# v2_1.net
KiCad netlist of a schematic drawn in EAGLE
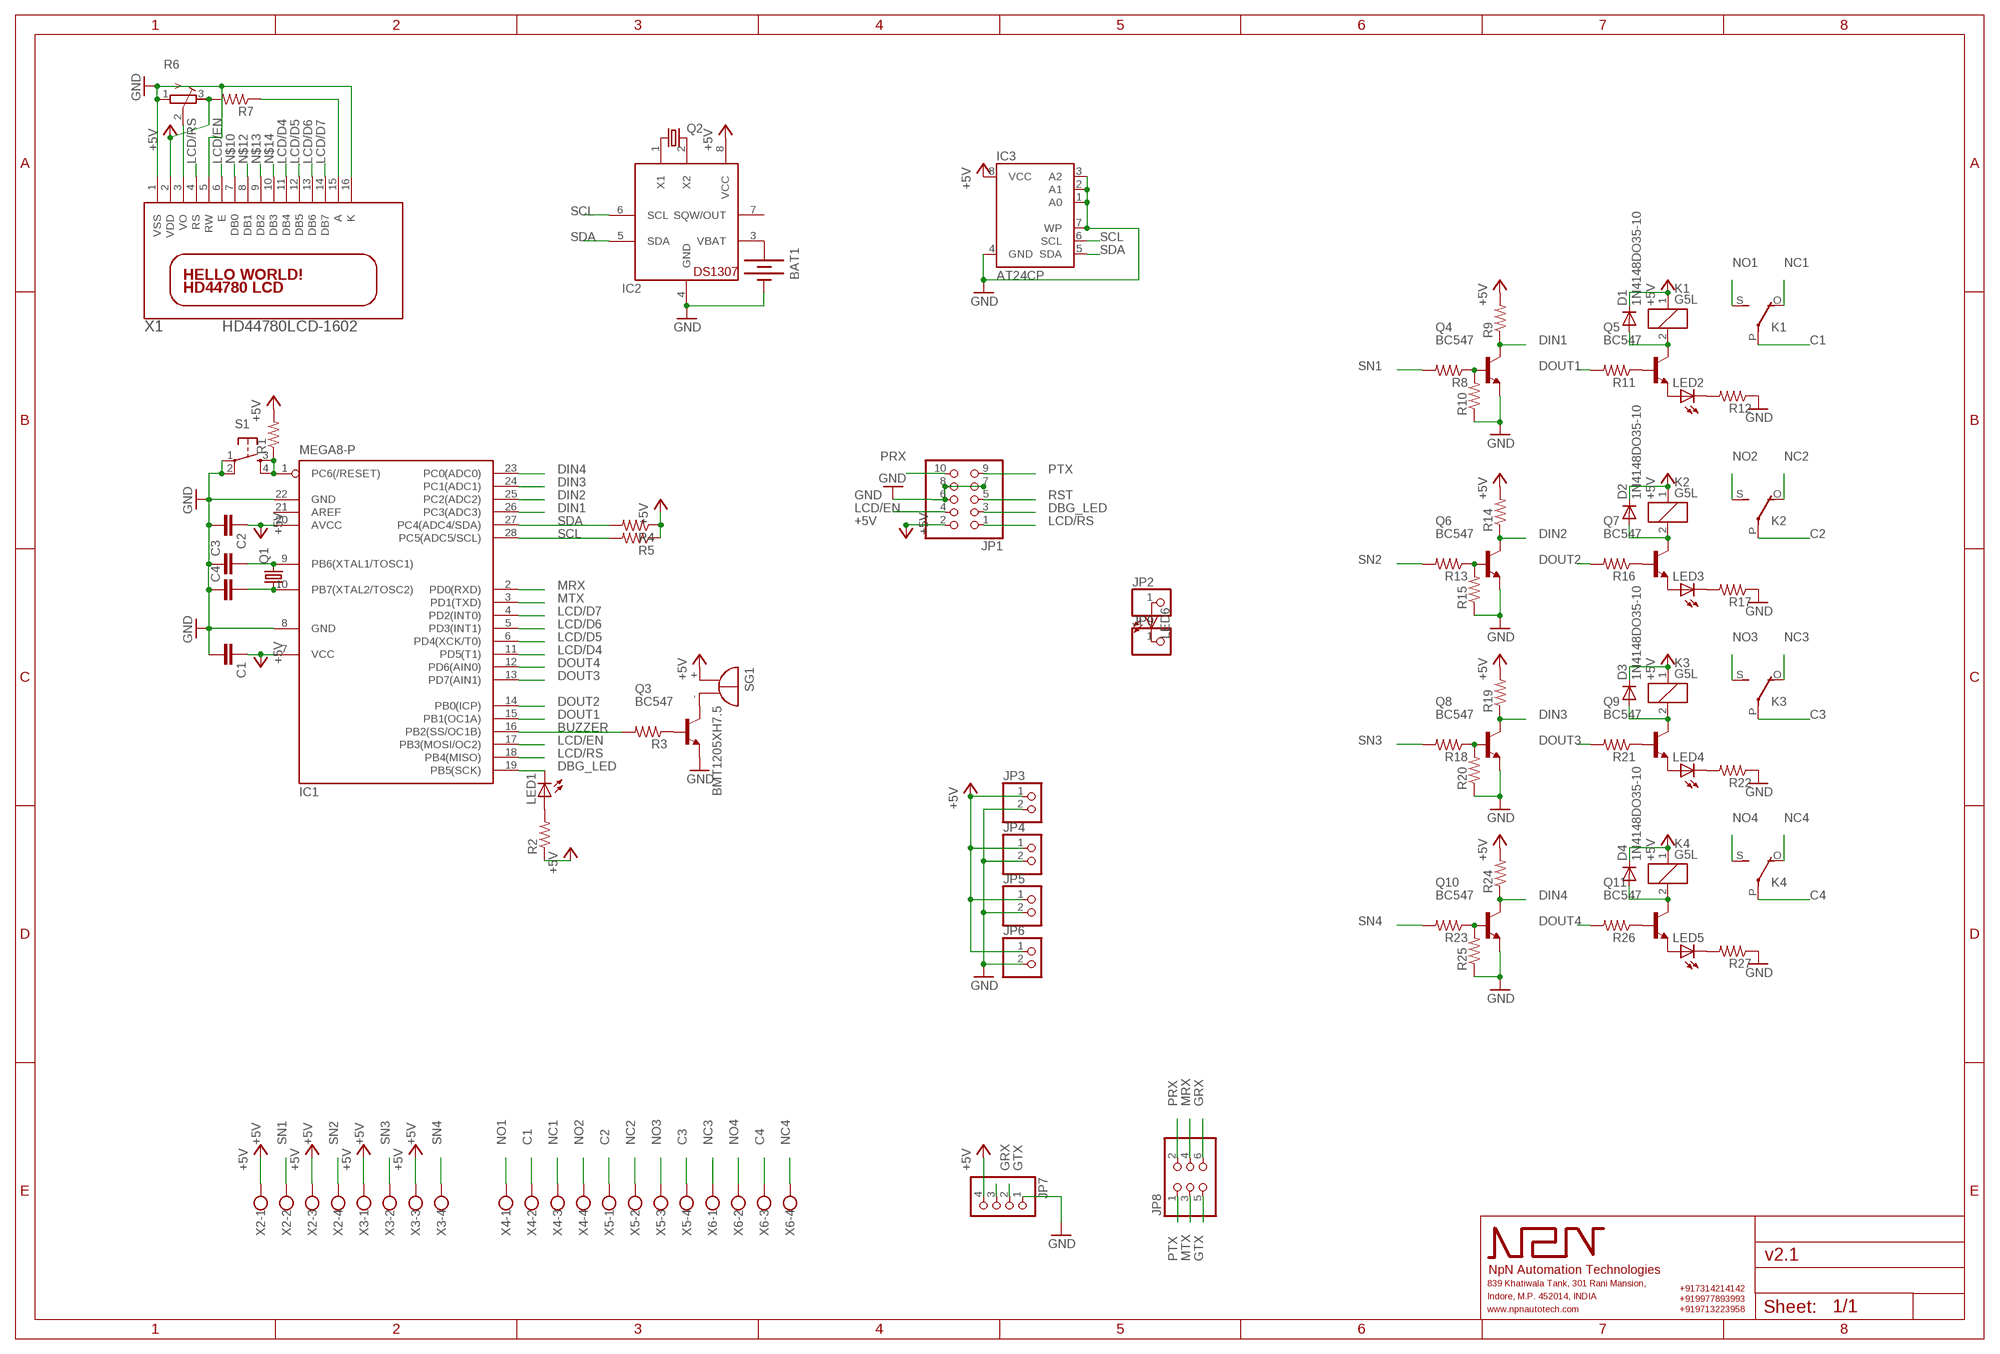
[diagram p0: schematic, sheet 1]

(export (version "E")
  (design (tool "Eeschema 10.0.6"))
  (components
    (comp (ref "BAT1")
      (value "BATTERY20PTH")
      (footprint "eagle-import:BATTCOM_20MM_PTH")
      (libsource (lib "eagle-import") (part "BATTERY20PTH"))
    )
    (comp (ref "C1")
      (value "C-EU050-025X075")
      (footprint "eagle-import:C050-025X075")
      (libsource (lib "eagle-import") (part "C-EU050-025X075"))
    )
    (comp (ref "C2")
      (value "C-EU050-025X075")
      (footprint "eagle-import:C050-025X075")
      (libsource (lib "eagle-import") (part "C-EU050-025X075"))
    )
    (comp (ref "C3")
      (value "C-EU050-025X075")
      (footprint "eagle-import:C050-025X075")
      (libsource (lib "eagle-import") (part "C-EU050-025X075"))
    )
    (comp (ref "C4")
      (value "C-EU050-025X075")
      (footprint "eagle-import:C050-025X075")
      (libsource (lib "eagle-import") (part "C-EU050-025X075"))
    )
    (comp (ref "D1")
      (value "1N4148DO35-10")
      (footprint "eagle-import:DO35-10")
      (libsource (lib "eagle-import") (part "1N4148DO35-10"))
    )
    (comp (ref "D2")
      (value "1N4148DO35-10")
      (footprint "eagle-import:DO35-10")
      (libsource (lib "eagle-import") (part "1N4148DO35-10"))
    )
    (comp (ref "D3")
      (value "1N4148DO35-10")
      (footprint "eagle-import:DO35-10")
      (libsource (lib "eagle-import") (part "1N4148DO35-10"))
    )
    (comp (ref "D4")
      (value "1N4148DO35-10")
      (footprint "eagle-import:DO35-10")
      (libsource (lib "eagle-import") (part "1N4148DO35-10"))
    )
    (comp (ref "IC1")
      (value "MEGA8-P")
      (footprint "eagle-import:DIL28-3")
      (libsource (lib "eagle-import") (part "MEGA8-P"))
    )
    (comp (ref "IC2")
      (value "DS1307")
      (footprint "eagle-import:DIL08")
      (libsource (lib "eagle-import") (part "DS1307"))
    )
    (comp (ref "IC3")
      (value "AT24CP")
      (footprint "eagle-import:DIL08")
      (fields (field (name "MPN") "AT24C1024BW-SH-B"))
      (libsource (lib "eagle-import") (part "AT24CP"))
    )
    (comp (ref "JP1")
      (value "PINHD-2X5")
      (footprint "eagle-import:2X05")
      (libsource (lib "eagle-import") (part "PINHD-2X5"))
    )
    (comp (ref "JP2")
      (value "PINHD-1X1")
      (footprint "eagle-import:1X01")
      (libsource (lib "eagle-import") (part "PINHD-1X1"))
    )
    (comp (ref "JP3")
      (value "PINHD-1X2")
      (footprint "eagle-import:1X02")
      (libsource (lib "eagle-import") (part "PINHD-1X2"))
    )
    (comp (ref "JP4")
      (value "PINHD-1X2")
      (footprint "eagle-import:1X02")
      (libsource (lib "eagle-import") (part "PINHD-1X2"))
    )
    (comp (ref "JP5")
      (value "PINHD-1X2")
      (footprint "eagle-import:1X02")
      (libsource (lib "eagle-import") (part "PINHD-1X2"))
    )
    (comp (ref "JP6")
      (value "PINHD-1X2")
      (footprint "eagle-import:1X02")
      (libsource (lib "eagle-import") (part "PINHD-1X2"))
    )
    (comp (ref "JP7")
      (value "PINHD-1X4")
      (footprint "eagle-import:1X04")
      (libsource (lib "eagle-import") (part "PINHD-1X4"))
    )
    (comp (ref "JP8")
      (value "PINHD-2X3")
      (footprint "eagle-import:2X03")
      (libsource (lib "eagle-import") (part "PINHD-2X3"))
    )
    (comp (ref "JP9")
      (value "PINHD-1X1")
      (footprint "eagle-import:1X01")
      (libsource (lib "eagle-import") (part "PINHD-1X1"))
    )
    (comp (ref "K1")
      (value "G5L")
      (footprint "eagle-import:G5LE")
      (libsource (lib "eagle-import") (part "G5L"))
    )
    (comp (ref "K2")
      (value "G5L")
      (footprint "eagle-import:G5LE")
      (libsource (lib "eagle-import") (part "G5L"))
    )
    (comp (ref "K3")
      (value "G5L")
      (footprint "eagle-import:G5LE")
      (libsource (lib "eagle-import") (part "G5L"))
    )
    (comp (ref "K4")
      (value "G5L")
      (footprint "eagle-import:G5LE")
      (libsource (lib "eagle-import") (part "G5L"))
    )
    (comp (ref "LED1")
      (value "LED5MM")
      (footprint "eagle-import:LED5MM")
      (libsource (lib "eagle-import") (part "LED5MM"))
    )
    (comp (ref "LED2")
      (value "LED5MM")
      (footprint "eagle-import:LED5MM")
      (libsource (lib "eagle-import") (part "LED5MM"))
    )
    (comp (ref "LED3")
      (value "LED5MM")
      (footprint "eagle-import:LED5MM")
      (libsource (lib "eagle-import") (part "LED5MM"))
    )
    (comp (ref "LED4")
      (value "LED5MM")
      (footprint "eagle-import:LED5MM")
      (libsource (lib "eagle-import") (part "LED5MM"))
    )
    (comp (ref "LED5")
      (value "LED5MM")
      (footprint "eagle-import:LED5MM")
      (libsource (lib "eagle-import") (part "LED5MM"))
    )
    (comp (ref "LED6")
      (value "LED5MM")
      (footprint "eagle-import:LED5MM")
      (libsource (lib "eagle-import") (part "LED5MM"))
    )
    (comp (ref "Q1")
      (value "CRYSTALHC49U-V")
      (footprint "eagle-import:HC49U-V")
      (libsource (lib "eagle-import") (part "CRYSTALHC49U-V"))
    )
    (comp (ref "Q2")
      (value "CRYSTALTC38H")
      (footprint "eagle-import:TC38H")
      (libsource (lib "eagle-import") (part "CRYSTALTC38H"))
    )
    (comp (ref "Q3")
      (value "BC547")
      (footprint "eagle-import:TO92")
      (libsource (lib "eagle-import") (part "BC547"))
    )
    (comp (ref "Q4")
      (value "BC547")
      (footprint "eagle-import:TO92")
      (libsource (lib "eagle-import") (part "BC547"))
    )
    (comp (ref "Q5")
      (value "BC547")
      (footprint "eagle-import:TO92")
      (libsource (lib "eagle-import") (part "BC547"))
    )
    (comp (ref "Q6")
      (value "BC547")
      (footprint "eagle-import:TO92")
      (libsource (lib "eagle-import") (part "BC547"))
    )
    (comp (ref "Q7")
      (value "BC547")
      (footprint "eagle-import:TO92")
      (libsource (lib "eagle-import") (part "BC547"))
    )
    (comp (ref "Q8")
      (value "BC547")
      (footprint "eagle-import:TO92")
      (libsource (lib "eagle-import") (part "BC547"))
    )
    (comp (ref "Q9")
      (value "BC547")
      (footprint "eagle-import:TO92")
      (libsource (lib "eagle-import") (part "BC547"))
    )
    (comp (ref "Q10")
      (value "BC547")
      (footprint "eagle-import:TO92")
      (libsource (lib "eagle-import") (part "BC547"))
    )
    (comp (ref "Q11")
      (value "BC547")
      (footprint "eagle-import:TO92")
      (libsource (lib "eagle-import") (part "BC547"))
    )
    (comp (ref "R1")
      (value "R-US_0207/10")
      (footprint "eagle-import:0207_10")
      (libsource (lib "eagle-import") (part "R-US_0207/10"))
    )
    (comp (ref "R2")
      (value "R-US_0207/10")
      (footprint "eagle-import:0207_10")
      (libsource (lib "eagle-import") (part "R-US_0207/10"))
    )
    (comp (ref "R3")
      (value "R-US_0207/10")
      (footprint "eagle-import:0207_10")
      (libsource (lib "eagle-import") (part "R-US_0207/10"))
    )
    (comp (ref "R4")
      (value "R-US_0207/10")
      (footprint "eagle-import:0207_10")
      (libsource (lib "eagle-import") (part "R-US_0207/10"))
    )
    (comp (ref "R5")
      (value "R-US_0207/10")
      (footprint "eagle-import:0207_10")
      (libsource (lib "eagle-import") (part "R-US_0207/10"))
    )
    (comp (ref "R6")
      (value "R-TRIMM3339P")
      (footprint "eagle-import:RTRIM3339P")
      (libsource (lib "eagle-import") (part "R-TRIMM3339P"))
    )
    (comp (ref "R7")
      (value "R-US_0207/10")
      (footprint "eagle-import:0207_10")
      (libsource (lib "eagle-import") (part "R-US_0207/10"))
    )
    (comp (ref "R8")
      (value "R-US_0207/10")
      (footprint "eagle-import:0207_10")
      (libsource (lib "eagle-import") (part "R-US_0207/10"))
    )
    (comp (ref "R9")
      (value "R-US_0207/10")
      (footprint "eagle-import:0207_10")
      (libsource (lib "eagle-import") (part "R-US_0207/10"))
    )
    (comp (ref "R10")
      (value "R-US_0207/10")
      (footprint "eagle-import:0207_10")
      (libsource (lib "eagle-import") (part "R-US_0207/10"))
    )
    (comp (ref "R11")
      (value "R-US_0207/10")
      (footprint "eagle-import:0207_10")
      (libsource (lib "eagle-import") (part "R-US_0207/10"))
    )
    (comp (ref "R12")
      (value "R-US_0207/10")
      (footprint "eagle-import:0207_10")
      (libsource (lib "eagle-import") (part "R-US_0207/10"))
    )
    (comp (ref "R13")
      (value "R-US_0207/10")
      (footprint "eagle-import:0207_10")
      (libsource (lib "eagle-import") (part "R-US_0207/10"))
    )
    (comp (ref "R14")
      (value "R-US_0207/10")
      (footprint "eagle-import:0207_10")
      (libsource (lib "eagle-import") (part "R-US_0207/10"))
    )
    (comp (ref "R15")
      (value "R-US_0207/10")
      (footprint "eagle-import:0207_10")
      (libsource (lib "eagle-import") (part "R-US_0207/10"))
    )
    (comp (ref "R16")
      (value "R-US_0207/10")
      (footprint "eagle-import:0207_10")
      (libsource (lib "eagle-import") (part "R-US_0207/10"))
    )
    (comp (ref "R17")
      (value "R-US_0207/10")
      (footprint "eagle-import:0207_10")
      (libsource (lib "eagle-import") (part "R-US_0207/10"))
    )
    (comp (ref "R18")
      (value "R-US_0207/10")
      (footprint "eagle-import:0207_10")
      (libsource (lib "eagle-import") (part "R-US_0207/10"))
    )
    (comp (ref "R19")
      (value "R-US_0207/10")
      (footprint "eagle-import:0207_10")
      (libsource (lib "eagle-import") (part "R-US_0207/10"))
    )
    (comp (ref "R20")
      (value "R-US_0207/10")
      (footprint "eagle-import:0207_10")
      (libsource (lib "eagle-import") (part "R-US_0207/10"))
    )
    (comp (ref "R21")
      (value "R-US_0207/10")
      (footprint "eagle-import:0207_10")
      (libsource (lib "eagle-import") (part "R-US_0207/10"))
    )
    (comp (ref "R22")
      (value "R-US_0207/10")
      (footprint "eagle-import:0207_10")
      (libsource (lib "eagle-import") (part "R-US_0207/10"))
    )
    (comp (ref "R23")
      (value "R-US_0207/10")
      (footprint "eagle-import:0207_10")
      (libsource (lib "eagle-import") (part "R-US_0207/10"))
    )
    (comp (ref "R24")
      (value "R-US_0207/10")
      (footprint "eagle-import:0207_10")
      (libsource (lib "eagle-import") (part "R-US_0207/10"))
    )
    (comp (ref "R25")
      (value "R-US_0207/10")
      (footprint "eagle-import:0207_10")
      (libsource (lib "eagle-import") (part "R-US_0207/10"))
    )
    (comp (ref "R26")
      (value "R-US_0207/10")
      (footprint "eagle-import:0207_10")
      (libsource (lib "eagle-import") (part "R-US_0207/10"))
    )
    (comp (ref "R27")
      (value "R-US_0207/10")
      (footprint "eagle-import:0207_10")
      (libsource (lib "eagle-import") (part "R-US_0207/10"))
    )
    (comp (ref "S1")
      (value "TAC_SWITCHPTH")
      (footprint "eagle-import:TACTILE-PTH")
      (libsource (lib "eagle-import") (part "TAC_SWITCHPTH"))
    )
    (comp (ref "SG1")
      (value "BMT1205XH7.5")
      (footprint "eagle-import:BMT1205XH7.5")
      (libsource (lib "eagle-import") (part "BMT1205XH7.5"))
    )
    (comp (ref "X1")
      (value "HD44780LCD-1602")
      (footprint "eagle-import:LCD1602")
      (libsource (lib "eagle-import") (part "HD44780LCD-1602"))
    )
    (comp (ref "X2")
      (value "W237-4")
      (footprint "eagle-import:W237-4")
      (libsource (lib "eagle-import") (part "W237-4"))
    )
    (comp (ref "X3")
      (value "W237-4")
      (footprint "eagle-import:W237-4")
      (libsource (lib "eagle-import") (part "W237-4"))
    )
    (comp (ref "X4")
      (value "W237-4")
      (footprint "eagle-import:W237-4")
      (libsource (lib "eagle-import") (part "W237-4"))
    )
    (comp (ref "X5")
      (value "W237-4")
      (footprint "eagle-import:W237-4")
      (libsource (lib "eagle-import") (part "W237-4"))
    )
    (comp (ref "X6")
      (value "W237-4")
      (footprint "eagle-import:W237-4")
      (libsource (lib "eagle-import") (part "W237-4"))
    )
  )
  (nets
    (net (code "1") (name "+5V") (class "Default")
      (node (ref "C1") (pin "1") (pinfunction "1_1") (pintype "passive"))
      (node (ref "C2") (pin "1") (pinfunction "1_1") (pintype "passive"))
      (node (ref "D1") (pin "C") (pinfunction "C_C") (pintype "passive"))
      (node (ref "D2") (pin "C") (pinfunction "C_C") (pintype "passive"))
      (node (ref "D3") (pin "C") (pinfunction "C_C") (pintype "passive"))
      (node (ref "D4") (pin "C") (pinfunction "C_C") (pintype "passive"))
      (node (ref "IC1") (pin "20") (pinfunction "AVCC_20") (pintype "power_in"))
      (node (ref "IC1") (pin "7") (pinfunction "VCC_7") (pintype "power_in"))
      (node (ref "IC2") (pin "8") (pinfunction "VCC_8") (pintype "power_in"))
      (node (ref "IC3") (pin "8") (pinfunction "VCC_8") (pintype "power_in"))
      (node (ref "JP1") (pin "2") (pinfunction "2_2") (pintype "passive"))
      (node (ref "JP3") (pin "1") (pinfunction "1_1") (pintype "passive"))
      (node (ref "JP4") (pin "1") (pinfunction "1_1") (pintype "passive"))
      (node (ref "JP5") (pin "1") (pinfunction "1_1") (pintype "passive"))
      (node (ref "JP6") (pin "1") (pinfunction "1_1") (pintype "passive"))
      (node (ref "JP7") (pin "4") (pinfunction "4_4") (pintype "passive"))
      (node (ref "K1") (pin "1") (pinfunction "1_1") (pintype "passive"))
      (node (ref "K2") (pin "1") (pinfunction "1_1") (pintype "passive"))
      (node (ref "K3") (pin "1") (pinfunction "1_1") (pintype "passive"))
      (node (ref "K4") (pin "1") (pinfunction "1_1") (pintype "passive"))
      (node (ref "R1") (pin "2") (pinfunction "2_2") (pintype "passive"))
      (node (ref "R14") (pin "2") (pinfunction "2_2") (pintype "passive"))
      (node (ref "R19") (pin "2") (pinfunction "2_2") (pintype "passive"))
      (node (ref "R2") (pin "1") (pinfunction "1_1") (pintype "passive"))
      (node (ref "R24") (pin "2") (pinfunction "2_2") (pintype "passive"))
      (node (ref "R4") (pin "1") (pinfunction "1_1") (pintype "passive"))
      (node (ref "R5") (pin "1") (pinfunction "1_1") (pintype "passive"))
      (node (ref "R6") (pin "3") (pinfunction "E_3") (pintype "passive"))
      (node (ref "R7") (pin "2") (pinfunction "2_2") (pintype "passive"))
      (node (ref "R9") (pin "2") (pinfunction "2_2") (pintype "passive"))
      (node (ref "SG1") (pin "+") (pinfunction "+_+") (pintype "passive"))
      (node (ref "X1") (pin "2") (pinfunction "VDD_2") (pintype "power_in"))
      (node (ref "X2") (pin "1") (pinfunction "KL_1") (pintype "passive"))
      (node (ref "X2") (pin "3") (pinfunction "KL_3") (pintype "passive"))
      (node (ref "X3") (pin "1") (pinfunction "KL_1") (pintype "passive"))
      (node (ref "X3") (pin "3") (pinfunction "KL_3") (pintype "passive"))
    )
    (net (code "2") (name "/BUZZER") (class "Default")
      (node (ref "IC1") (pin "16") (pinfunction "PB2(SS/OC1B)_16") (pintype "bidirectional"))
      (node (ref "R3") (pin "2") (pinfunction "2_2") (pintype "passive"))
    )
    (net (code "3") (name "/C1") (class "Default")
      (node (ref "K1") (pin "P") (pinfunction "P_P") (pintype "passive"))
      (node (ref "X4") (pin "2") (pinfunction "KL_2") (pintype "passive"))
    )
    (net (code "4") (name "/C2") (class "Default")
      (node (ref "K2") (pin "P") (pinfunction "P_P") (pintype "passive"))
      (node (ref "X5") (pin "1") (pinfunction "KL_1") (pintype "passive"))
    )
    (net (code "5") (name "/C3") (class "Default")
      (node (ref "K3") (pin "P") (pinfunction "P_P") (pintype "passive"))
      (node (ref "X5") (pin "4") (pinfunction "KL_4") (pintype "passive"))
    )
    (net (code "6") (name "/C4") (class "Default")
      (node (ref "K4") (pin "P") (pinfunction "P_P") (pintype "passive"))
      (node (ref "X6") (pin "3") (pinfunction "KL_3") (pintype "passive"))
    )
    (net (code "7") (name "/DBG_LED") (class "Default")
      (node (ref "IC1") (pin "19") (pinfunction "PB5(SCK)_19") (pintype "bidirectional"))
      (node (ref "JP1") (pin "3") (pinfunction "3_3") (pintype "passive"))
      (node (ref "LED1") (pin "K") (pinfunction "C_K") (pintype "passive"))
    )
    (net (code "8") (name "/DIN1") (class "Default")
      (node (ref "IC1") (pin "26") (pinfunction "PC3(ADC3)_26") (pintype "bidirectional"))
      (node (ref "Q4") (pin "3") (pinfunction "C_3") (pintype "passive"))
      (node (ref "R9") (pin "1") (pinfunction "1_1") (pintype "passive"))
    )
    (net (code "9") (name "/DIN2") (class "Default")
      (node (ref "IC1") (pin "25") (pinfunction "PC2(ADC2)_25") (pintype "bidirectional"))
      (node (ref "Q6") (pin "3") (pinfunction "C_3") (pintype "passive"))
      (node (ref "R14") (pin "1") (pinfunction "1_1") (pintype "passive"))
    )
    (net (code "10") (name "/DIN3") (class "Default")
      (node (ref "IC1") (pin "24") (pinfunction "PC1(ADC1)_24") (pintype "bidirectional"))
      (node (ref "Q8") (pin "3") (pinfunction "C_3") (pintype "passive"))
      (node (ref "R19") (pin "1") (pinfunction "1_1") (pintype "passive"))
    )
    (net (code "11") (name "/DIN4") (class "Default")
      (node (ref "IC1") (pin "23") (pinfunction "PC0(ADC0)_23") (pintype "bidirectional"))
      (node (ref "Q10") (pin "3") (pinfunction "C_3") (pintype "passive"))
      (node (ref "R24") (pin "1") (pinfunction "1_1") (pintype "passive"))
    )
    (net (code "12") (name "/DOUT1") (class "Default")
      (node (ref "IC1") (pin "15") (pinfunction "PB1(OC1A)_15") (pintype "bidirectional"))
      (node (ref "R11") (pin "2") (pinfunction "2_2") (pintype "passive"))
    )
    (net (code "13") (name "/DOUT2") (class "Default")
      (node (ref "IC1") (pin "14") (pinfunction "PB0(ICP)_14") (pintype "bidirectional"))
      (node (ref "R16") (pin "2") (pinfunction "2_2") (pintype "passive"))
    )
    (net (code "14") (name "/DOUT3") (class "Default")
      (node (ref "IC1") (pin "13") (pinfunction "PD7(AIN1)_13") (pintype "bidirectional"))
      (node (ref "R21") (pin "2") (pinfunction "2_2") (pintype "passive"))
    )
    (net (code "15") (name "/DOUT4") (class "Default")
      (node (ref "IC1") (pin "12") (pinfunction "PD6(AIN0)_12") (pintype "bidirectional"))
      (node (ref "R26") (pin "2") (pinfunction "2_2") (pintype "passive"))
    )
    (net (code "16") (name "/GRX") (class "Default")
      (node (ref "JP7") (pin "3") (pinfunction "3_3") (pintype "passive"))
      (node (ref "JP8") (pin "6") (pinfunction "6_6") (pintype "passive"))
    )
    (net (code "17") (name "/GTX") (class "Default")
      (node (ref "JP7") (pin "2") (pinfunction "2_2") (pintype "passive"))
      (node (ref "JP8") (pin "5") (pinfunction "5_5") (pintype "passive"))
    )
    (net (code "18") (name "/LCD{slash}D4") (class "Default")
      (node (ref "IC1") (pin "11") (pinfunction "PD5(T1)_11") (pintype "bidirectional"))
      (node (ref "X1") (pin "11") (pinfunction "DB4_11") (pintype "bidirectional"))
    )
    (net (code "19") (name "/LCD{slash}D5") (class "Default")
      (node (ref "IC1") (pin "6") (pinfunction "PD4(XCK/T0)_6") (pintype "bidirectional"))
      (node (ref "X1") (pin "12") (pinfunction "DB5_12") (pintype "bidirectional"))
    )
    (net (code "20") (name "/LCD{slash}D6") (class "Default")
      (node (ref "IC1") (pin "5") (pinfunction "PD3(INT1)_5") (pintype "bidirectional"))
      (node (ref "X1") (pin "13") (pinfunction "DB6_13") (pintype "bidirectional"))
    )
    (net (code "21") (name "/LCD{slash}D7") (class "Default")
      (node (ref "IC1") (pin "4") (pinfunction "PD2(INT0)_4") (pintype "bidirectional"))
      (node (ref "X1") (pin "14") (pinfunction "DB7_14") (pintype "bidirectional"))
    )
    (net (code "22") (name "/LCD{slash}EN") (class "Default")
      (node (ref "IC1") (pin "17") (pinfunction "PB3(MOSI/OC2)_17") (pintype "bidirectional"))
      (node (ref "JP1") (pin "4") (pinfunction "4_4") (pintype "passive"))
      (node (ref "X1") (pin "6") (pinfunction "E_6") (pintype "input"))
    )
    (net (code "23") (name "/LCD{slash}RS") (class "Default")
      (node (ref "IC1") (pin "18") (pinfunction "PB4(MISO)_18") (pintype "bidirectional"))
      (node (ref "JP1") (pin "1") (pinfunction "1_1") (pintype "passive"))
      (node (ref "X1") (pin "4") (pinfunction "RS_4") (pintype "input"))
    )
    (net (code "24") (name "/MRX") (class "Default")
      (node (ref "IC1") (pin "2") (pinfunction "PD0(RXD)_2") (pintype "bidirectional"))
      (node (ref "JP8") (pin "4") (pinfunction "4_4") (pintype "passive"))
    )
    (net (code "25") (name "/MTX") (class "Default")
      (node (ref "IC1") (pin "3") (pinfunction "PD1(TXD)_3") (pintype "bidirectional"))
      (node (ref "JP8") (pin "3") (pinfunction "3_3") (pintype "passive"))
    )
    (net (code "26") (name "/N$10") (class "Default")
      (node (ref "X1") (pin "7") (pinfunction "DB0_7") (pintype "bidirectional"))
    )
    (net (code "27") (name "/N$12") (class "Default")
      (node (ref "X1") (pin "8") (pinfunction "DB1_8") (pintype "bidirectional"))
    )
    (net (code "28") (name "/N$13") (class "Default")
      (node (ref "X1") (pin "9") (pinfunction "DB2_9") (pintype "bidirectional"))
    )
    (net (code "29") (name "/N$14") (class "Default")
      (node (ref "X1") (pin "10") (pinfunction "DB3_10") (pintype "bidirectional"))
    )
    (net (code "30") (name "/NC1") (class "Default")
      (node (ref "K1") (pin "O") (pinfunction "O_O") (pintype "passive"))
      (node (ref "X4") (pin "3") (pinfunction "KL_3") (pintype "passive"))
    )
    (net (code "31") (name "/NC2") (class "Default")
      (node (ref "K2") (pin "O") (pinfunction "O_O") (pintype "passive"))
      (node (ref "X5") (pin "2") (pinfunction "KL_2") (pintype "passive"))
    )
    (net (code "32") (name "/NC3") (class "Default")
      (node (ref "K3") (pin "O") (pinfunction "O_O") (pintype "passive"))
      (node (ref "X6") (pin "1") (pinfunction "KL_1") (pintype "passive"))
    )
    (net (code "33") (name "/NC4") (class "Default")
      (node (ref "K4") (pin "O") (pinfunction "O_O") (pintype "passive"))
      (node (ref "X6") (pin "4") (pinfunction "KL_4") (pintype "passive"))
    )
    (net (code "34") (name "/NO1") (class "Default")
      (node (ref "K1") (pin "S") (pinfunction "S_S") (pintype "passive"))
      (node (ref "X4") (pin "1") (pinfunction "KL_1") (pintype "passive"))
    )
    (net (code "35") (name "/NO2") (class "Default")
      (node (ref "K2") (pin "S") (pinfunction "S_S") (pintype "passive"))
      (node (ref "X4") (pin "4") (pinfunction "KL_4") (pintype "passive"))
    )
    (net (code "36") (name "/NO3") (class "Default")
      (node (ref "K3") (pin "S") (pinfunction "S_S") (pintype "passive"))
      (node (ref "X5") (pin "3") (pinfunction "KL_3") (pintype "passive"))
    )
    (net (code "37") (name "/NO4") (class "Default")
      (node (ref "K4") (pin "S") (pinfunction "S_S") (pintype "passive"))
      (node (ref "X6") (pin "2") (pinfunction "KL_2") (pintype "passive"))
    )
    (net (code "38") (name "/PRX") (class "Default")
      (node (ref "JP1") (pin "10") (pinfunction "10_10") (pintype "passive"))
      (node (ref "JP8") (pin "2") (pinfunction "2_2") (pintype "passive"))
    )
    (net (code "39") (name "/PTX") (class "Default")
      (node (ref "JP1") (pin "9") (pinfunction "9_9") (pintype "passive"))
      (node (ref "JP8") (pin "1") (pinfunction "1_1") (pintype "passive"))
    )
    (net (code "40") (name "/RST") (class "Default")
      (node (ref "IC1") (pin "1") (pinfunction "PC6(/RESET)_1") (pintype "bidirectional"))
      (node (ref "JP1") (pin "5") (pinfunction "5_5") (pintype "passive"))
      (node (ref "R1") (pin "1") (pinfunction "1_1") (pintype "passive"))
      (node (ref "S1") (pin "3") (pinfunction "3_3") (pintype "passive"))
      (node (ref "S1") (pin "4") (pinfunction "4_4") (pintype "passive"))
    )
    (net (code "41") (name "/SCL") (class "Default")
      (node (ref "IC1") (pin "28") (pinfunction "PC5(ADC5/SCL)_28") (pintype "bidirectional"))
      (node (ref "IC2") (pin "6") (pinfunction "SCL_6") (pintype "bidirectional"))
      (node (ref "IC3") (pin "6") (pinfunction "SCL_6") (pintype "bidirectional"))
      (node (ref "R5") (pin "2") (pinfunction "2_2") (pintype "passive"))
    )
    (net (code "42") (name "/SDA") (class "Default")
      (node (ref "IC1") (pin "27") (pinfunction "PC4(ADC4/SDA)_27") (pintype "bidirectional"))
      (node (ref "IC2") (pin "5") (pinfunction "SDA_5") (pintype "bidirectional"))
      (node (ref "IC3") (pin "5") (pinfunction "SDA_5") (pintype "bidirectional"))
      (node (ref "R4") (pin "2") (pinfunction "2_2") (pintype "passive"))
    )
    (net (code "43") (name "/SN1") (class "Default")
      (node (ref "R8") (pin "2") (pinfunction "2_2") (pintype "passive"))
      (node (ref "X2") (pin "2") (pinfunction "KL_2") (pintype "passive"))
    )
    (net (code "44") (name "/SN2") (class "Default")
      (node (ref "R13") (pin "2") (pinfunction "2_2") (pintype "passive"))
      (node (ref "X2") (pin "4") (pinfunction "KL_4") (pintype "passive"))
    )
    (net (code "45") (name "/SN3") (class "Default")
      (node (ref "R18") (pin "2") (pinfunction "2_2") (pintype "passive"))
      (node (ref "X3") (pin "2") (pinfunction "KL_2") (pintype "passive"))
    )
    (net (code "46") (name "/SN4") (class "Default")
      (node (ref "R23") (pin "2") (pinfunction "2_2") (pintype "passive"))
      (node (ref "X3") (pin "4") (pinfunction "KL_4") (pintype "passive"))
    )
    (net (code "47") (name "GND") (class "Default")
      (node (ref "BAT1") (pin "2") (pinfunction "-_2") (pintype "power_in"))
      (node (ref "C1") (pin "2") (pinfunction "2_2") (pintype "passive"))
      (node (ref "C2") (pin "2") (pinfunction "2_2") (pintype "passive"))
      (node (ref "C3") (pin "1") (pinfunction "1_1") (pintype "passive"))
      (node (ref "C4") (pin "1") (pinfunction "1_1") (pintype "passive"))
      (node (ref "IC1") (pin "22") (pinfunction "GND_22") (pintype "power_in"))
      (node (ref "IC1") (pin "8") (pinfunction "GND_8") (pintype "power_in"))
      (node (ref "IC2") (pin "4") (pinfunction "GND_4") (pintype "power_in"))
      (node (ref "IC3") (pin "1") (pinfunction "A0_1") (pintype "input"))
      (node (ref "IC3") (pin "2") (pinfunction "A1_2") (pintype "input"))
      (node (ref "IC3") (pin "3") (pinfunction "A2_3") (pintype "input"))
      (node (ref "IC3") (pin "4") (pinfunction "GND_4") (pintype "power_in"))
      (node (ref "IC3") (pin "7") (pinfunction "WP_7") (pintype "input"))
      (node (ref "JP1") (pin "6") (pinfunction "6_6") (pintype "passive"))
      (node (ref "JP1") (pin "7") (pinfunction "7_7") (pintype "passive"))
      (node (ref "JP1") (pin "8") (pinfunction "8_8") (pintype "passive"))
      (node (ref "JP3") (pin "2") (pinfunction "2_2") (pintype "passive"))
      (node (ref "JP4") (pin "2") (pinfunction "2_2") (pintype "passive"))
      (node (ref "JP5") (pin "2") (pinfunction "2_2") (pintype "passive"))
      (node (ref "JP6") (pin "2") (pinfunction "2_2") (pintype "passive"))
      (node (ref "JP7") (pin "1") (pinfunction "1_1") (pintype "passive"))
      (node (ref "Q10") (pin "1") (pinfunction "E_1") (pintype "passive"))
      (node (ref "Q3") (pin "1") (pinfunction "E_1") (pintype "passive"))
      (node (ref "Q4") (pin "1") (pinfunction "E_1") (pintype "passive"))
      (node (ref "Q6") (pin "1") (pinfunction "E_1") (pintype "passive"))
      (node (ref "Q8") (pin "1") (pinfunction "E_1") (pintype "passive"))
      (node (ref "R10") (pin "1") (pinfunction "1_1") (pintype "passive"))
      (node (ref "R12") (pin "1") (pinfunction "1_1") (pintype "passive"))
      (node (ref "R15") (pin "1") (pinfunction "1_1") (pintype "passive"))
      (node (ref "R17") (pin "1") (pinfunction "1_1") (pintype "passive"))
      (node (ref "R20") (pin "1") (pinfunction "1_1") (pintype "passive"))
      (node (ref "R22") (pin "1") (pinfunction "1_1") (pintype "passive"))
      (node (ref "R25") (pin "1") (pinfunction "1_1") (pintype "passive"))
      (node (ref "R27") (pin "1") (pinfunction "1_1") (pintype "passive"))
      (node (ref "R6") (pin "1") (pinfunction "A_1") (pintype "passive"))
      (node (ref "S1") (pin "1") (pinfunction "1_1") (pintype "passive"))
      (node (ref "S1") (pin "2") (pinfunction "2_2") (pintype "passive"))
      (node (ref "X1") (pin "1") (pinfunction "VSS_1") (pintype "power_in"))
      (node (ref "X1") (pin "16") (pinfunction "K_16") (pintype "input"))
      (node (ref "X1") (pin "5") (pinfunction "RW_5") (pintype "input"))
    )
    (net (code "48") (name "Net-(BAT1-+)") (class "Default")
      (node (ref "BAT1") (pin "1") (pinfunction "+_1") (pintype "power_in"))
      (node (ref "IC2") (pin "3") (pinfunction "VBAT_3") (pintype "power_in"))
    )
    (net (code "49") (name "Net-(IC1-PB6(XTAL1{slash}TOSC1))") (class "Default")
      (node (ref "C3") (pin "2") (pinfunction "2_2") (pintype "passive"))
      (node (ref "IC1") (pin "9") (pinfunction "PB6(XTAL1/TOSC1)_9") (pintype "bidirectional"))
      (node (ref "Q1") (pin "2") (pinfunction "2_2") (pintype "passive"))
    )
    (net (code "50") (name "Net-(IC1-PB7(XTAL2{slash}TOSC2))") (class "Default")
      (node (ref "C4") (pin "2") (pinfunction "2_2") (pintype "passive"))
      (node (ref "IC1") (pin "10") (pinfunction "PB7(XTAL2/TOSC2)_10") (pintype "bidirectional"))
      (node (ref "Q1") (pin "1") (pinfunction "1_1") (pintype "passive"))
    )
    (net (code "51") (name "Net-(IC2-X1)") (class "Default")
      (node (ref "IC2") (pin "1") (pinfunction "X1_1") (pintype "passive"))
      (node (ref "Q2") (pin "1") (pinfunction "1_1") (pintype "passive"))
    )
    (net (code "52") (name "Net-(IC2-X2)") (class "Default")
      (node (ref "IC2") (pin "2") (pinfunction "X2_2") (pintype "passive"))
      (node (ref "Q2") (pin "2") (pinfunction "2_2") (pintype "passive"))
    )
    (net (code "53") (name "Net-(JP2-Pad1)") (class "Default")
      (node (ref "JP2") (pin "1") (pinfunction "1_1") (pintype "passive"))
      (node (ref "LED6") (pin "A") (pinfunction "A_A") (pintype "passive"))
    )
    (net (code "54") (name "Net-(LED1-PadA)") (class "Default")
      (node (ref "LED1") (pin "A") (pinfunction "A_A") (pintype "passive"))
      (node (ref "R2") (pin "2") (pinfunction "2_2") (pintype "passive"))
    )
    (net (code "55") (name "Net-(LED2-C)") (class "Default")
      (node (ref "LED2") (pin "K") (pinfunction "C_K") (pintype "passive"))
      (node (ref "R12") (pin "2") (pinfunction "2_2") (pintype "passive"))
    )
    (net (code "56") (name "Net-(LED3-C)") (class "Default")
      (node (ref "LED3") (pin "K") (pinfunction "C_K") (pintype "passive"))
      (node (ref "R17") (pin "2") (pinfunction "2_2") (pintype "passive"))
    )
    (net (code "57") (name "Net-(LED4-C)") (class "Default")
      (node (ref "LED4") (pin "K") (pinfunction "C_K") (pintype "passive"))
      (node (ref "R22") (pin "2") (pinfunction "2_2") (pintype "passive"))
    )
    (net (code "58") (name "Net-(LED5-C)") (class "Default")
      (node (ref "LED5") (pin "K") (pinfunction "C_K") (pintype "passive"))
      (node (ref "R27") (pin "2") (pinfunction "2_2") (pintype "passive"))
    )
    (net (code "59") (name "Net-(LED6-C)") (class "Default")
      (node (ref "JP9") (pin "1") (pinfunction "1_1") (pintype "passive"))
      (node (ref "LED6") (pin "K") (pinfunction "C_K") (pintype "passive"))
    )
    (net (code "60") (name "Net-(Q3-B)") (class "Default")
      (node (ref "Q3") (pin "2") (pinfunction "B_2") (pintype "passive"))
      (node (ref "R3") (pin "1") (pinfunction "1_1") (pintype "passive"))
    )
    (net (code "61") (name "Net-(Q3-C)") (class "Default")
      (node (ref "Q3") (pin "3") (pinfunction "C_3") (pintype "passive"))
      (node (ref "SG1") (pin "-") (pinfunction "-_-") (pintype "passive"))
    )
    (net (code "62") (name "Net-(Q4-B)") (class "Default")
      (node (ref "Q4") (pin "2") (pinfunction "B_2") (pintype "passive"))
      (node (ref "R10") (pin "2") (pinfunction "2_2") (pintype "passive"))
      (node (ref "R8") (pin "1") (pinfunction "1_1") (pintype "passive"))
    )
    (net (code "63") (name "Net-(Q5-B)") (class "Default")
      (node (ref "Q5") (pin "2") (pinfunction "B_2") (pintype "passive"))
      (node (ref "R11") (pin "1") (pinfunction "1_1") (pintype "passive"))
    )
    (net (code "64") (name "Net-(Q5-C)") (class "Default")
      (node (ref "D1") (pin "A") (pinfunction "A_A") (pintype "passive"))
      (node (ref "K1") (pin "2") (pinfunction "2_2") (pintype "passive"))
      (node (ref "Q5") (pin "3") (pinfunction "C_3") (pintype "passive"))
    )
    (net (code "65") (name "Net-(Q5-E)") (class "Default")
      (node (ref "LED2") (pin "A") (pinfunction "A_A") (pintype "passive"))
      (node (ref "Q5") (pin "1") (pinfunction "E_1") (pintype "passive"))
    )
    (net (code "66") (name "Net-(Q6-B)") (class "Default")
      (node (ref "Q6") (pin "2") (pinfunction "B_2") (pintype "passive"))
      (node (ref "R13") (pin "1") (pinfunction "1_1") (pintype "passive"))
      (node (ref "R15") (pin "2") (pinfunction "2_2") (pintype "passive"))
    )
    (net (code "67") (name "Net-(Q7-B)") (class "Default")
      (node (ref "Q7") (pin "2") (pinfunction "B_2") (pintype "passive"))
      (node (ref "R16") (pin "1") (pinfunction "1_1") (pintype "passive"))
    )
    (net (code "68") (name "Net-(Q7-C)") (class "Default")
      (node (ref "D2") (pin "A") (pinfunction "A_A") (pintype "passive"))
      (node (ref "K2") (pin "2") (pinfunction "2_2") (pintype "passive"))
      (node (ref "Q7") (pin "3") (pinfunction "C_3") (pintype "passive"))
    )
    (net (code "69") (name "Net-(Q7-E)") (class "Default")
      (node (ref "LED3") (pin "A") (pinfunction "A_A") (pintype "passive"))
      (node (ref "Q7") (pin "1") (pinfunction "E_1") (pintype "passive"))
    )
    (net (code "70") (name "Net-(Q8-B)") (class "Default")
      (node (ref "Q8") (pin "2") (pinfunction "B_2") (pintype "passive"))
      (node (ref "R18") (pin "1") (pinfunction "1_1") (pintype "passive"))
      (node (ref "R20") (pin "2") (pinfunction "2_2") (pintype "passive"))
    )
    (net (code "71") (name "Net-(Q9-B)") (class "Default")
      (node (ref "Q9") (pin "2") (pinfunction "B_2") (pintype "passive"))
      (node (ref "R21") (pin "1") (pinfunction "1_1") (pintype "passive"))
    )
    (net (code "72") (name "Net-(Q9-C)") (class "Default")
      (node (ref "D3") (pin "A") (pinfunction "A_A") (pintype "passive"))
      (node (ref "K3") (pin "2") (pinfunction "2_2") (pintype "passive"))
      (node (ref "Q9") (pin "3") (pinfunction "C_3") (pintype "passive"))
    )
    (net (code "73") (name "Net-(Q9-E)") (class "Default")
      (node (ref "LED4") (pin "A") (pinfunction "A_A") (pintype "passive"))
      (node (ref "Q9") (pin "1") (pinfunction "E_1") (pintype "passive"))
    )
    (net (code "74") (name "Net-(Q10-B)") (class "Default")
      (node (ref "Q10") (pin "2") (pinfunction "B_2") (pintype "passive"))
      (node (ref "R23") (pin "1") (pinfunction "1_1") (pintype "passive"))
      (node (ref "R25") (pin "2") (pinfunction "2_2") (pintype "passive"))
    )
    (net (code "75") (name "Net-(Q11-B)") (class "Default")
      (node (ref "Q11") (pin "2") (pinfunction "B_2") (pintype "passive"))
      (node (ref "R26") (pin "1") (pinfunction "1_1") (pintype "passive"))
    )
    (net (code "76") (name "Net-(Q11-C)") (class "Default")
      (node (ref "D4") (pin "A") (pinfunction "A_A") (pintype "passive"))
      (node (ref "K4") (pin "2") (pinfunction "2_2") (pintype "passive"))
      (node (ref "Q11") (pin "3") (pinfunction "C_3") (pintype "passive"))
    )
    (net (code "77") (name "Net-(Q11-E)") (class "Default")
      (node (ref "LED5") (pin "A") (pinfunction "A_A") (pintype "passive"))
      (node (ref "Q11") (pin "1") (pinfunction "E_1") (pintype "passive"))
    )
    (net (code "78") (name "Net-(R6-S)") (class "Default")
      (node (ref "R6") (pin "2") (pinfunction "S_2") (pintype "passive"))
      (node (ref "X1") (pin "3") (pinfunction "VO_3") (pintype "input"))
    )
    (net (code "79") (name "Net-(X1-A)") (class "Default")
      (node (ref "R7") (pin "1") (pinfunction "1_1") (pintype "passive"))
      (node (ref "X1") (pin "15") (pinfunction "A_15") (pintype "input"))
    )
    (net (code "80") (name "unconnected-(IC1-AREF-Pad21)") (class "Default")
      (node (ref "IC1") (pin "21") (pinfunction "AREF_21") (pintype "passive"))
    )
    (net (code "81") (name "unconnected-(IC2-SQW{slash}OUT-Pad7)") (class "Default")
      (node (ref "IC2") (pin "7") (pinfunction "SQW/OUT_7") (pintype "bidirectional"))
    )
  )
)
